# Power_9_5v_LP2985.net
KiCad netlist of a schematic drawn in EAGLE
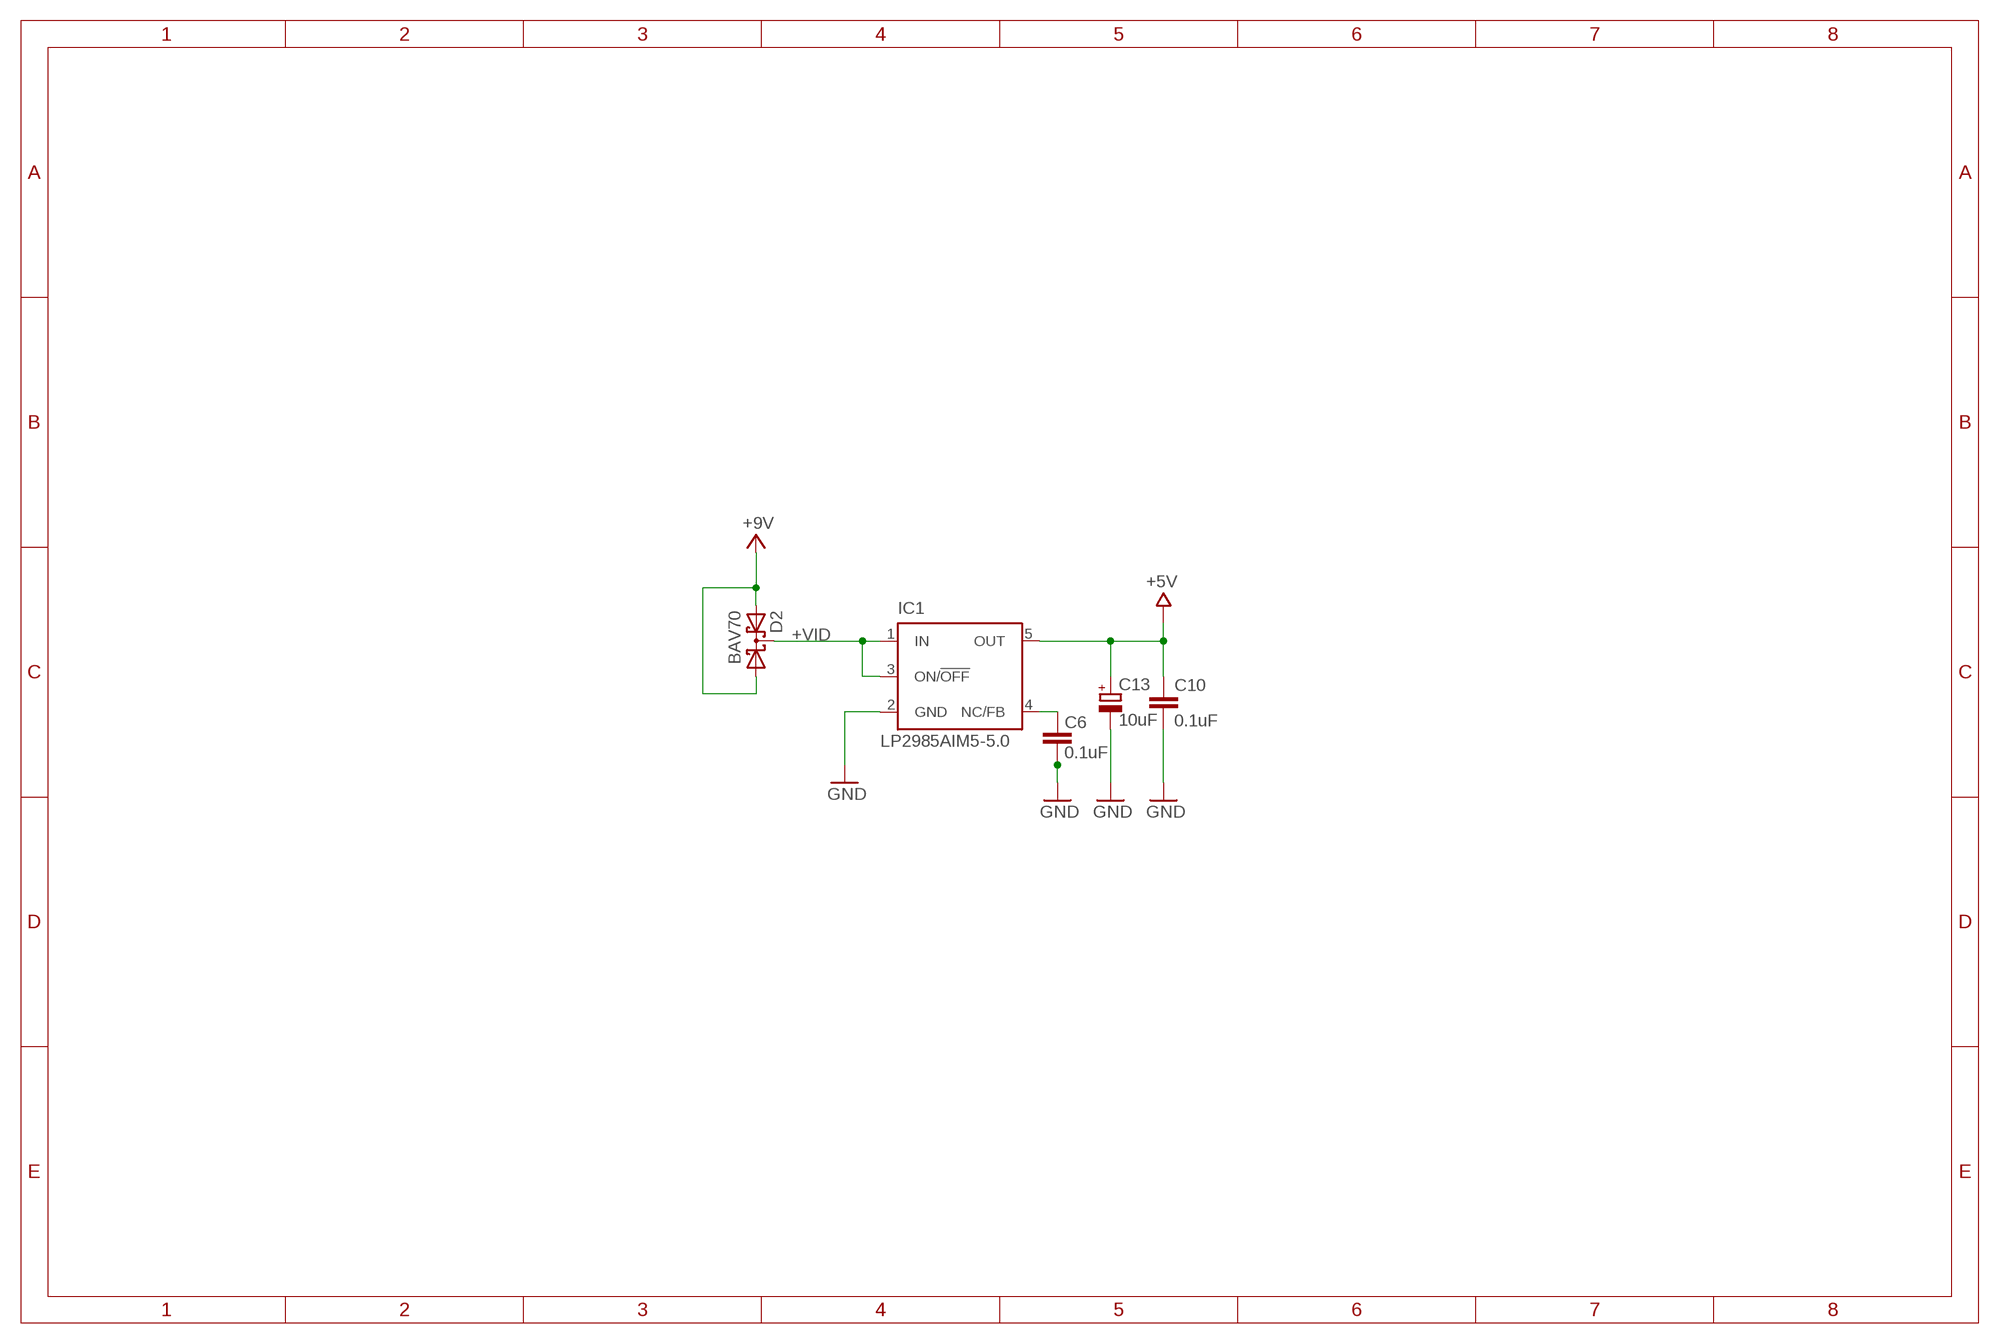
[diagram p0: schematic, sheet 1]

(export (version "E")
  (design (tool "Eeschema 10.0.6"))
  (components
    (comp (ref "C6")
      (value "0.1uF")
      (footprint "eagle-import:C0603-ROUND")
      (libsource (lib "eagle-import") (part "C-EUC0603"))
    )
    (comp (ref "C10")
      (value "0.1uF")
      (footprint "eagle-import:C0603-ROUND")
      (libsource (lib "eagle-import") (part "C-EUC0603"))
    )
    (comp (ref "C13")
      (value "10uF")
      (footprint "eagle-import:SMC_B")
      (libsource (lib "eagle-import") (part "CPOL-EUSMCB"))
    )
    (comp (ref "D2")
      (value "BAV70")
      (footprint "eagle-import:SOT23")
      (libsource (lib "eagle-import") (part "BAS70-05"))
    )
    (comp (ref "IC1")
      (value "LP2985AIM5-5.0")
      (footprint "eagle-import:SOT23-DBV")
      (libsource (lib "eagle-import") (part "LP2985-XXDBVR50"))
    )
  )
  (nets
    (net (code "1") (name "+5V") (class "Default")
      (node (ref "C10") (pin "1") (pinfunction "1_1") (pintype "passive"))
      (node (ref "C13") (pin "+") (pinfunction "+_+") (pintype "passive"))
      (node (ref "IC1") (pin "5") (pinfunction "OUT_5") (pintype "passive"))
    )
    (net (code "2") (name "+9V") (class "Default")
      (node (ref "D2") (pin "1") (pinfunction "A1_1") (pintype "passive"))
      (node (ref "D2") (pin "2") (pinfunction "A2_2") (pintype "passive"))
    )
    (net (code "3") (name "/+VID") (class "Default")
      (node (ref "D2") (pin "3") (pinfunction "C_3") (pintype "passive"))
      (node (ref "IC1") (pin "1") (pinfunction "IN_1") (pintype "input"))
      (node (ref "IC1") (pin "3") (pinfunction "ON/~{OFF}_3") (pintype "input"))
    )
    (net (code "4") (name "GND") (class "Default")
      (node (ref "C10") (pin "2") (pinfunction "2_2") (pintype "passive"))
      (node (ref "C13") (pin "-") (pinfunction "-_-") (pintype "passive"))
      (node (ref "C6") (pin "1") (pinfunction "1_1") (pintype "passive"))
      (node (ref "IC1") (pin "2") (pinfunction "GND_2") (pintype "power_in"))
    )
    (net (code "5") (name "Net-(IC1-NC{slash}FB)") (class "Default")
      (node (ref "C6") (pin "2") (pinfunction "2_2") (pintype "passive"))
      (node (ref "IC1") (pin "4") (pinfunction "NC/FB_4") (pintype "passive"))
    )
  )
)
